# ANA_FE_1_2.net
KiCad netlist of a schematic drawn in Altium Designer
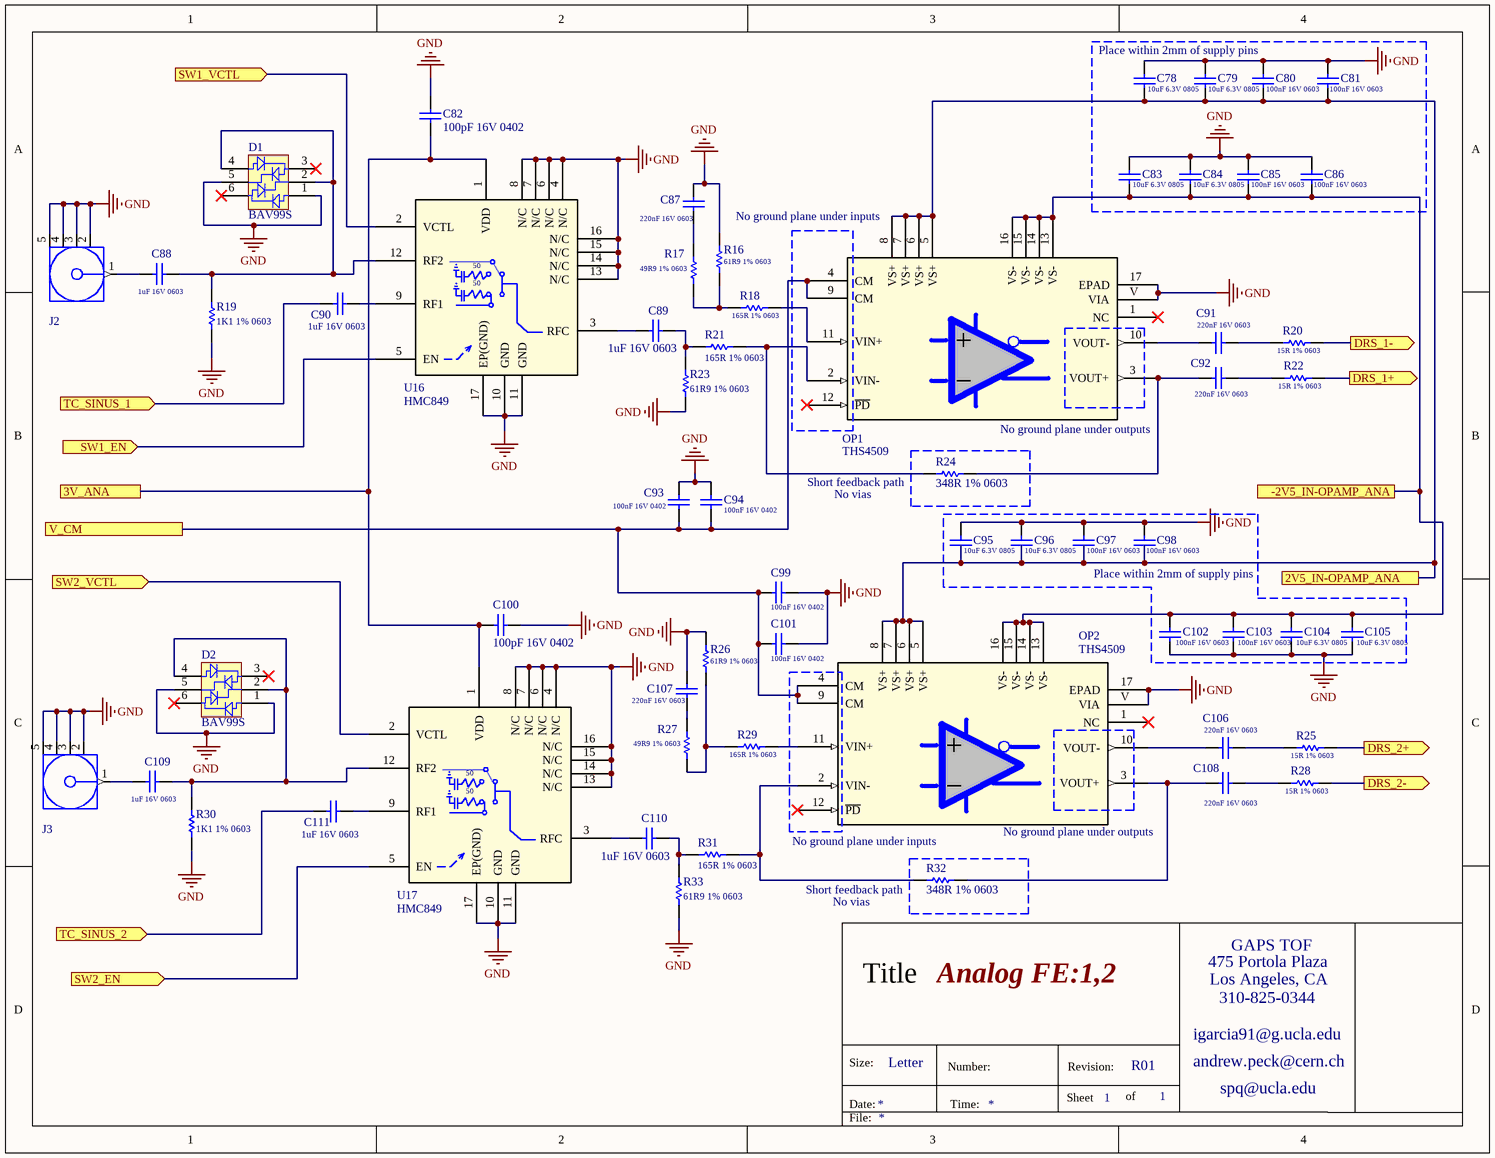
[diagram p0: ANA_FE_1_2.SchDoc]

(export (version "E")
  (design (tool "Eeschema 10.0.6"))
  (components
    (comp (ref "C78")
      (value "10uF 6.3V 0805")
      (footprint "CAPC0805(2012)145_L")
      (description "CAP 10uF 6.3V ±10% 0805 (2012 Metric) Thickness 1.45mm SMD")
      (fields (field (name "TOLERANCE") "Â±10%"))
      (libsource (lib "Altium Content Vault") (part "CAP"))
    )
    (comp (ref "C79")
      (value "10uF 6.3V 0805")
      (footprint "CAPC0805(2012)145_L")
      (description "CAP 10uF 6.3V ±10% 0805 (2012 Metric) Thickness 1.45mm SMD")
      (fields (field (name "TOLERANCE") "Â±10%"))
      (libsource (lib "Altium Content Vault") (part "CAP"))
    )
    (comp (ref "C80")
      (value "100nF 16V 0603")
      (footprint "CAPC0603(1608)100_N")
      (description "CAP 100nF 16V ±20% 0603 (1608 Metric) Thickness 1mm SMD")
      (fields (field (name "TOLERANCE") "Â±20%"))
      (libsource (lib "Altium Content Vault") (part "CAP"))
    )
    (comp (ref "C81")
      (value "100nF 16V 0603")
      (footprint "CAPC0603(1608)100_N")
      (description "CAP 100nF 16V ±20% 0603 (1608 Metric) Thickness 1mm SMD")
      (fields (field (name "TOLERANCE") "Â±20%"))
      (libsource (lib "Altium Content Vault") (part "CAP"))
    )
    (comp (ref "C82")
      (value "100pF 16V 0402")
      (footprint "CAPC0402(1005)60_M")
      (description "CAP 100pF 16V ±5% 0402 (1005 Metric) Thickness 0.6mm SMD")
      (fields (field (name "TOLERANCE") "Â±5%"))
      (libsource (lib "Altium Content Vault") (part "CAP"))
    )
    (comp (ref "C83")
      (value "10uF 6.3V 0805")
      (footprint "CAPC0805(2012)145_L")
      (description "CAP 10uF 6.3V ±10% 0805 (2012 Metric) Thickness 1.45mm SMD")
      (fields (field (name "TOLERANCE") "Â±10%"))
      (libsource (lib "Altium Content Vault") (part "CAP"))
    )
    (comp (ref "C84")
      (value "10uF 6.3V 0805")
      (footprint "CAPC0805(2012)145_L")
      (description "CAP 10uF 6.3V ±10% 0805 (2012 Metric) Thickness 1.45mm SMD")
      (fields (field (name "TOLERANCE") "Â±10%"))
      (libsource (lib "Altium Content Vault") (part "CAP"))
    )
    (comp (ref "C85")
      (value "100nF 16V 0603")
      (footprint "CAPC0603(1608)100_N")
      (description "CAP 100nF 16V ±20% 0603 (1608 Metric) Thickness 1mm SMD")
      (fields (field (name "TOLERANCE") "Â±20%"))
      (libsource (lib "Altium Content Vault") (part "CAP"))
    )
    (comp (ref "C86")
      (value "100nF 16V 0603")
      (footprint "CAPC0603(1608)100_N")
      (description "CAP 100nF 16V ±20% 0603 (1608 Metric) Thickness 1mm SMD")
      (fields (field (name "TOLERANCE") "Â±20%"))
      (libsource (lib "Altium Content Vault") (part "CAP"))
    )
    (comp (ref "C87")
      (value "220nF 16V 0603")
      (footprint "CAPC0603(1608)100_M")
      (description "CAP 220nF 16V ±10% 0603 (1608 Metric) Thickness 1mm SMD")
      (fields (field (name "TOLERANCE") "Â±10%"))
      (libsource (lib "Altium Content Vault") (part "CAP"))
    )
    (comp (ref "C88")
      (value "1uF 16V 0603")
      (footprint "CAPC0603(1608)100_N")
      (description "CAP 1uF 16V ±5% 0603 (1608 Metric) Thickness 1mm SMD")
      (fields (field (name "TOLERANCE") "Â±5%"))
      (libsource (lib "Altium Content Vault") (part "CAP"))
    )
    (comp (ref "C89")
      (value "1uF 16V 0603")
      (footprint "CAPC0603(1608)100_N")
      (description "CAP 1uF 16V ±5% 0603 (1608 Metric) Thickness 1mm SMD")
      (fields (field (name "TOLERANCE") "Â±5%"))
      (libsource (lib "Altium Content Vault") (part "CAP"))
    )
    (comp (ref "C90")
      (value "1uF 16V 0603")
      (footprint "CAPC0603(1608)100_N")
      (description "CAP 1uF 16V ±5% 0603 (1608 Metric) Thickness 1mm SMD")
      (fields (field (name "TOLERANCE") "Â±5%"))
      (libsource (lib "Altium Content Vault") (part "CAP"))
    )
    (comp (ref "C91")
      (value "220nF 16V 0603")
      (footprint "CAPC0603(1608)100_M")
      (description "CAP 220nF 16V ±10% 0603 (1608 Metric) Thickness 1mm SMD")
      (fields (field (name "TOLERANCE") "Â±10%"))
      (libsource (lib "Altium Content Vault") (part "CAP"))
    )
    (comp (ref "C92")
      (value "220nF 16V 0603")
      (footprint "CAPC0603(1608)100_M")
      (description "CAP 220nF 16V ±10% 0603 (1608 Metric) Thickness 1mm SMD")
      (fields (field (name "TOLERANCE") "Â±10%"))
      (libsource (lib "Altium Content Vault") (part "CAP"))
    )
    (comp (ref "C93")
      (value "100nF 16V 0402")
      (footprint "CAPC0402(1005)60_M")
      (description "CAP 100nF 16V ±20% 0402 (1005 Metric) Thickness 0.6mm SMD")
      (fields (field (name "TOLERANCE") "Â±20%"))
      (libsource (lib "Altium Content Vault") (part "CAP"))
    )
    (comp (ref "C94")
      (value "100nF 16V 0402")
      (footprint "CAPC0402(1005)60_M")
      (description "CAP 100nF 16V ±20% 0402 (1005 Metric) Thickness 0.6mm SMD")
      (fields (field (name "TOLERANCE") "Â±20%"))
      (libsource (lib "Altium Content Vault") (part "CAP"))
    )
    (comp (ref "C95")
      (value "10uF 6.3V 0805")
      (footprint "CAPC0805(2012)145_L")
      (description "CAP 10uF 6.3V ±10% 0805 (2012 Metric) Thickness 1.45mm SMD")
      (fields (field (name "TOLERANCE") "Â±10%"))
      (libsource (lib "Altium Content Vault") (part "CAP"))
    )
    (comp (ref "C96")
      (value "10uF 6.3V 0805")
      (footprint "CAPC0805(2012)145_L")
      (description "CAP 10uF 6.3V ±10% 0805 (2012 Metric) Thickness 1.45mm SMD")
      (fields (field (name "TOLERANCE") "Â±10%"))
      (libsource (lib "Altium Content Vault") (part "CAP"))
    )
    (comp (ref "C97")
      (value "100nF 16V 0603")
      (footprint "CAPC0603(1608)100_N")
      (description "CAP 100nF 16V ±20% 0603 (1608 Metric) Thickness 1mm SMD")
      (fields (field (name "TOLERANCE") "Â±20%"))
      (libsource (lib "Altium Content Vault") (part "CAP"))
    )
    (comp (ref "C98")
      (value "100nF 16V 0603")
      (footprint "CAPC0603(1608)100_N")
      (description "CAP 100nF 16V ±20% 0603 (1608 Metric) Thickness 1mm SMD")
      (fields (field (name "TOLERANCE") "Â±20%"))
      (libsource (lib "Altium Content Vault") (part "CAP"))
    )
    (comp (ref "C99")
      (value "100nF 16V 0402")
      (footprint "CAPC0402(1005)60_M")
      (description "CAP 100nF 16V ±20% 0402 (1005 Metric) Thickness 0.6mm SMD")
      (fields (field (name "TOLERANCE") "Â±20%"))
      (libsource (lib "Altium Content Vault") (part "CAP"))
    )
    (comp (ref "C100")
      (value "100pF 16V 0402")
      (footprint "CAPC0402(1005)60_M")
      (description "CAP 100pF 16V ±5% 0402 (1005 Metric) Thickness 0.6mm SMD")
      (fields (field (name "TOLERANCE") "Â±5%"))
      (libsource (lib "Altium Content Vault") (part "CAP"))
    )
    (comp (ref "C101")
      (value "100nF 16V 0402")
      (footprint "CAPC0402(1005)60_M")
      (description "CAP 100nF 16V ±20% 0402 (1005 Metric) Thickness 0.6mm SMD")
      (fields (field (name "TOLERANCE") "Â±20%"))
      (libsource (lib "Altium Content Vault") (part "CAP"))
    )
    (comp (ref "C102")
      (value "100nF 16V 0603")
      (footprint "CAPC0603(1608)100_N")
      (description "CAP 100nF 16V ±20% 0603 (1608 Metric) Thickness 1mm SMD")
      (fields (field (name "TOLERANCE") "Â±20%"))
      (libsource (lib "Altium Content Vault") (part "CAP"))
    )
    (comp (ref "C103")
      (value "100nF 16V 0603")
      (footprint "CAPC0603(1608)100_N")
      (description "CAP 100nF 16V ±20% 0603 (1608 Metric) Thickness 1mm SMD")
      (fields (field (name "TOLERANCE") "Â±20%"))
      (libsource (lib "Altium Content Vault") (part "CAP"))
    )
    (comp (ref "C104")
      (value "10uF 6.3V 0805")
      (footprint "CAPC0805(2012)145_L")
      (description "CAP 10uF 6.3V ±10% 0805 (2012 Metric) Thickness 1.45mm SMD")
      (fields (field (name "TOLERANCE") "Â±10%"))
      (libsource (lib "Altium Content Vault") (part "CAP"))
    )
    (comp (ref "C105")
      (value "10uF 6.3V 0805")
      (footprint "CAPC0805(2012)145_L")
      (description "CAP 10uF 6.3V ±10% 0805 (2012 Metric) Thickness 1.45mm SMD")
      (fields (field (name "TOLERANCE") "Â±10%"))
      (libsource (lib "Altium Content Vault") (part "CAP"))
    )
    (comp (ref "C106")
      (value "220nF 16V 0603")
      (footprint "CAPC0603(1608)100_M")
      (description "CAP 220nF 16V ±10% 0603 (1608 Metric) Thickness 1mm SMD")
      (fields (field (name "TOLERANCE") "Â±10%"))
      (libsource (lib "Altium Content Vault") (part "CAP"))
    )
    (comp (ref "C107")
      (value "220nF 16V 0603")
      (footprint "CAPC0603(1608)100_M")
      (description "CAP 220nF 16V ±10% 0603 (1608 Metric) Thickness 1mm SMD")
      (fields (field (name "TOLERANCE") "Â±10%"))
      (libsource (lib "Altium Content Vault") (part "CAP"))
    )
    (comp (ref "C108")
      (value "220nF 16V 0603")
      (footprint "CAPC0603(1608)100_M")
      (description "CAP 220nF 16V ±10% 0603 (1608 Metric) Thickness 1mm SMD")
      (fields (field (name "TOLERANCE") "Â±10%"))
      (libsource (lib "Altium Content Vault") (part "CAP"))
    )
    (comp (ref "C109")
      (value "1uF 16V 0603")
      (footprint "CAPC0603(1608)100_N")
      (description "CAP 1uF 16V ±5% 0603 (1608 Metric) Thickness 1mm SMD")
      (fields (field (name "TOLERANCE") "Â±5%"))
      (libsource (lib "Altium Content Vault") (part "CAP"))
    )
    (comp (ref "C110")
      (value "1uF 16V 0603")
      (footprint "CAPC0603(1608)100_N")
      (description "CAP 1uF 16V ±5% 0603 (1608 Metric) Thickness 1mm SMD")
      (fields (field (name "TOLERANCE") "Â±5%"))
      (libsource (lib "Altium Content Vault") (part "CAP"))
    )
    (comp (ref "C111")
      (value "1uF 16V 0603")
      (footprint "CAPC0603(1608)100_N")
      (description "CAP 1uF 16V ±5% 0603 (1608 Metric) Thickness 1mm SMD")
      (fields (field (name "TOLERANCE") "Â±5%"))
      (libsource (lib "Altium Content Vault") (part "CAP"))
    )
    (comp (ref "D1")
      (value "BAV99S")
      (footprint "INF-SOT363_V")
      (description "Silicon Switching Diode, SOT363, Reel, Green")
      (fields (field (name "MANUFACTURER") "Infineon"))
      (libsource (lib "Altium Content Vault") (part "INF-D_A1K2C3A4K5C6-6"))
    )
    (comp (ref "D2")
      (value "BAV99S")
      (footprint "INF-SOT363_V")
      (description "Silicon Switching Diode, SOT363, Reel, Green")
      (fields (field (name "MANUFACTURER") "Infineon"))
      (libsource (lib "Altium Content Vault") (part "INF-D_A1K2C3A4K5C6-6"))
    )
    (comp (ref "J2")
      (value "CONREVSMA003.062")
      (footprint "CON-SMA-EDGE062")
      (libsource (lib "Altium Content Vault") (part "CN-1P-F-RF5"))
    )
    (comp (ref "J3")
      (value "CONREVSMA003.062")
      (footprint "CON-SMA-EDGE062")
      (libsource (lib "Altium Content Vault") (part "CN-1P-F-RF5"))
    )
    (comp (ref "OP1")
      (value "THS4509")
      (footprint "RGT16")
      (description "Imported")
      (fields (field (name "MANUFACTURER_PART_NUMBER") "THS4509RGTT"))
      (libsource (lib "THS4509RGTT") (part "THS4509RGTT"))
    )
    (comp (ref "OP2")
      (value "THS4509")
      (footprint "RGT16")
      (description "Imported")
      (fields (field (name "MANUFACTURER_PART_NUMBER") "THS4509RGTT"))
      (libsource (lib "THS4509RGTT") (part "THS4509RGTT"))
    )
    (comp (ref "R16")
      (value "61R9 1% 0603")
      (footprint "RESC0603(1608)_M")
      (description "61R9 0.1W 1% 0603 (1608 Metric)  SMD")
      (fields (field (name "TOLERANCE") "1 %") (field (name "POWER") "0.1 W"))
      (libsource (lib "Altium Content Vault") (part "RES"))
    )
    (comp (ref "R17")
      (value "49R9 1% 0603")
      (footprint "RESC0603(1608)_N")
      (description "49R9 0.1W 1% 0603 (1608 Metric)  SMD")
      (fields (field (name "POWER") "0.1 W") (field (name "TOLERANCE") "1 %"))
      (libsource (lib "Altium Content Vault") (part "RES"))
    )
    (comp (ref "R18")
      (value "165R 1% 0603")
      (footprint "RESC0603(1608)_M")
      (description "165R 0.1W 1% 0603 (1608 Metric)  SMD")
      (fields (field (name "TOLERANCE") "1 %") (field (name "POWER") "0.1 W"))
      (libsource (lib "Altium Content Vault") (part "RES"))
    )
    (comp (ref "R19")
      (value "1K1 1% 0603")
      (footprint "RESC0603(1608)_N")
      (description "1K1 0.1W 1% 0603 (1608 Metric)  SMD")
      (fields (field (name "TOLERANCE") "1 %") (field (name "POWER") "0.1 W"))
      (libsource (lib "Altium Content Vault") (part "RES"))
    )
    (comp (ref "R20")
      (value "15R 1% 0603")
      (footprint "RESC0603(1608)_M")
      (description "15R 0.1W 1% 0603 (1608 Metric)  SMD")
      (fields (field (name "TOLERANCE") "1 %") (field (name "POWER") "0.1 W"))
      (libsource (lib "Altium Content Vault") (part "RES"))
    )
    (comp (ref "R21")
      (value "165R 1% 0603")
      (footprint "RESC0603(1608)_M")
      (description "165R 0.1W 1% 0603 (1608 Metric)  SMD")
      (fields (field (name "TOLERANCE") "1 %") (field (name "POWER") "0.1 W"))
      (libsource (lib "Altium Content Vault") (part "RES"))
    )
    (comp (ref "R22")
      (value "15R 1% 0603")
      (footprint "RESC0603(1608)_M")
      (description "15R 0.1W 1% 0603 (1608 Metric)  SMD")
      (fields (field (name "TOLERANCE") "1 %") (field (name "POWER") "0.1 W"))
      (libsource (lib "Altium Content Vault") (part "RES"))
    )
    (comp (ref "R23")
      (value "61R9 1% 0603")
      (footprint "RESC0603(1608)_M")
      (description "61R9 0.1W 1% 0603 (1608 Metric)  SMD")
      (fields (field (name "TOLERANCE") "1 %") (field (name "POWER") "0.1 W"))
      (libsource (lib "Altium Content Vault") (part "RES"))
    )
    (comp (ref "R24")
      (value "348R 1% 0603")
      (footprint "RESC0603(1608)_N")
      (description "348R 0.1W 1% 0603 (1608 Metric)  SMD")
      (fields (field (name "POWER") "0.1 W") (field (name "TOLERANCE") "1 %"))
      (libsource (lib "Altium Content Vault") (part "RES"))
    )
    (comp (ref "R25")
      (value "15R 1% 0603")
      (footprint "RESC0603(1608)_M")
      (description "15R 0.1W 1% 0603 (1608 Metric)  SMD")
      (fields (field (name "TOLERANCE") "1 %") (field (name "POWER") "0.1 W"))
      (libsource (lib "Altium Content Vault") (part "RES"))
    )
    (comp (ref "R26")
      (value "61R9 1% 0603")
      (footprint "RESC0603(1608)_M")
      (description "61R9 0.1W 1% 0603 (1608 Metric)  SMD")
      (fields (field (name "TOLERANCE") "1 %") (field (name "POWER") "0.1 W"))
      (libsource (lib "Altium Content Vault") (part "RES"))
    )
    (comp (ref "R27")
      (value "49R9 1% 0603")
      (footprint "RESC0603(1608)_N")
      (description "49R9 0.1W 1% 0603 (1608 Metric)  SMD")
      (fields (field (name "POWER") "0.1 W") (field (name "TOLERANCE") "1 %"))
      (libsource (lib "Altium Content Vault") (part "RES"))
    )
    (comp (ref "R28")
      (value "15R 1% 0603")
      (footprint "RESC0603(1608)_M")
      (description "15R 0.1W 1% 0603 (1608 Metric)  SMD")
      (fields (field (name "TOLERANCE") "1 %") (field (name "POWER") "0.1 W"))
      (libsource (lib "Altium Content Vault") (part "RES"))
    )
    (comp (ref "R29")
      (value "165R 1% 0603")
      (footprint "RESC0603(1608)_M")
      (description "165R 0.1W 1% 0603 (1608 Metric)  SMD")
      (fields (field (name "TOLERANCE") "1 %") (field (name "POWER") "0.1 W"))
      (libsource (lib "Altium Content Vault") (part "RES"))
    )
    (comp (ref "R30")
      (value "1K1 1% 0603")
      (footprint "RESC0603(1608)_N")
      (description "1K1 0.1W 1% 0603 (1608 Metric)  SMD")
      (fields (field (name "TOLERANCE") "1 %") (field (name "POWER") "0.1 W"))
      (libsource (lib "Altium Content Vault") (part "RES"))
    )
    (comp (ref "R31")
      (value "165R 1% 0603")
      (footprint "RESC0603(1608)_M")
      (description "165R 0.1W 1% 0603 (1608 Metric)  SMD")
      (fields (field (name "TOLERANCE") "1 %") (field (name "POWER") "0.1 W"))
      (libsource (lib "Altium Content Vault") (part "RES"))
    )
    (comp (ref "R32")
      (value "348R 1% 0603")
      (footprint "RESC0603(1608)_N")
      (description "348R 0.1W 1% 0603 (1608 Metric)  SMD")
      (fields (field (name "POWER") "0.1 W") (field (name "TOLERANCE") "1 %"))
      (libsource (lib "Altium Content Vault") (part "RES"))
    )
    (comp (ref "R33")
      (value "61R9 1% 0603")
      (footprint "RESC0603(1608)_M")
      (description "61R9 0.1W 1% 0603 (1608 Metric)  SMD")
      (fields (field (name "TOLERANCE") "1 %") (field (name "POWER") "0.1 W"))
      (libsource (lib "Altium Content Vault") (part "RES"))
    )
    (comp (ref "U16")
      (value "HMC849")
      (footprint "CP_16_40")
      (description "Imported")
      (fields (field (name "MANUFACTURER_PART_NUMBER") "HMC849ALP4CE"))
      (libsource (lib "HMC849ALP4CE") (part "HMC849ALP4CE"))
    )
    (comp (ref "U17")
      (value "HMC849")
      (footprint "CP_16_40")
      (description "Imported")
      (fields (field (name "MANUFACTURER_PART_NUMBER") "HMC849ALP4CE"))
      (libsource (lib "HMC849ALP4CE") (part "HMC849ALP4CE"))
    )
  )
  (nets
    (net (code "1") (name "/-2V5_IN-OPAMP_ANA") (class "Default")
      (node (ref "C102") (pin "1") (pinfunction "1_1") (pintype "passive"))
      (node (ref "C103") (pin "1") (pinfunction "1_1") (pintype "passive"))
      (node (ref "C104") (pin "1") (pinfunction "1_1") (pintype "passive"))
      (node (ref "C105") (pin "1") (pinfunction "1_1") (pintype "passive"))
      (node (ref "C83") (pin "1") (pinfunction "1_1") (pintype "passive"))
      (node (ref "C84") (pin "1") (pinfunction "1_1") (pintype "passive"))
      (node (ref "C85") (pin "1") (pinfunction "1_1") (pintype "passive"))
      (node (ref "C86") (pin "1") (pinfunction "1_1") (pintype "passive"))
      (node (ref "OP1") (pin "13") (pinfunction "VS-_13") (pintype "power_in"))
      (node (ref "OP1") (pin "14") (pinfunction "VS-_14") (pintype "power_in"))
      (node (ref "OP1") (pin "15") (pinfunction "VS-_15") (pintype "power_in"))
      (node (ref "OP1") (pin "16") (pinfunction "VS-_16") (pintype "power_in"))
      (node (ref "OP2") (pin "13") (pinfunction "VS-_13") (pintype "power_in"))
      (node (ref "OP2") (pin "14") (pinfunction "VS-_14") (pintype "power_in"))
      (node (ref "OP2") (pin "15") (pinfunction "VS-_15") (pintype "power_in"))
      (node (ref "OP2") (pin "16") (pinfunction "VS-_16") (pintype "power_in"))
    )
    (net (code "2") (name "/2V5_IN-OPAMP_ANA") (class "Default")
      (node (ref "C78") (pin "1") (pinfunction "1_1") (pintype "passive"))
      (node (ref "C79") (pin "1") (pinfunction "1_1") (pintype "passive"))
      (node (ref "C80") (pin "1") (pinfunction "1_1") (pintype "passive"))
      (node (ref "C81") (pin "1") (pinfunction "1_1") (pintype "passive"))
      (node (ref "C95") (pin "1") (pinfunction "1_1") (pintype "passive"))
      (node (ref "C96") (pin "1") (pinfunction "1_1") (pintype "passive"))
      (node (ref "C97") (pin "1") (pinfunction "1_1") (pintype "passive"))
      (node (ref "C98") (pin "1") (pinfunction "1_1") (pintype "passive"))
      (node (ref "OP1") (pin "5") (pinfunction "VS+_5") (pintype "power_in"))
      (node (ref "OP1") (pin "6") (pinfunction "VS+_6") (pintype "power_in"))
      (node (ref "OP1") (pin "7") (pinfunction "VS+_7") (pintype "power_in"))
      (node (ref "OP1") (pin "8") (pinfunction "VS+_8") (pintype "power_in"))
      (node (ref "OP2") (pin "5") (pinfunction "VS+_5") (pintype "power_in"))
      (node (ref "OP2") (pin "6") (pinfunction "VS+_6") (pintype "power_in"))
      (node (ref "OP2") (pin "7") (pinfunction "VS+_7") (pintype "power_in"))
      (node (ref "OP2") (pin "8") (pinfunction "VS+_8") (pintype "power_in"))
    )
    (net (code "3") (name "/3V_ANA") (class "Default")
      (node (ref "C100") (pin "2") (pinfunction "2_2") (pintype "passive"))
      (node (ref "C82") (pin "1") (pinfunction "1_1") (pintype "passive"))
      (node (ref "U16") (pin "1") (pinfunction "VDD_1") (pintype "passive"))
      (node (ref "U17") (pin "1") (pinfunction "VDD_1") (pintype "passive"))
    )
    (net (code "4") (name "/DRS_1+") (class "Default")
      (node (ref "R22") (pin "2") (pinfunction "2_2") (pintype "passive"))
    )
    (net (code "5") (name "/DRS_1-") (class "Default")
      (node (ref "R20") (pin "2") (pinfunction "2_2") (pintype "passive"))
    )
    (net (code "6") (name "/DRS_2+") (class "Default")
      (node (ref "R25") (pin "2") (pinfunction "2_2") (pintype "passive"))
    )
    (net (code "7") (name "/DRS_2-") (class "Default")
      (node (ref "R28") (pin "2") (pinfunction "2_2") (pintype "passive"))
    )
    (net (code "8") (name "/SW1_EN") (class "Default")
      (node (ref "U16") (pin "5") (pinfunction "EN_5") (pintype "passive"))
    )
    (net (code "9") (name "/SW1_VCTL") (class "Default")
      (node (ref "U16") (pin "2") (pinfunction "VCTL_2") (pintype "passive"))
    )
    (net (code "10") (name "/SW2_EN") (class "Default")
      (node (ref "U17") (pin "5") (pinfunction "EN_5") (pintype "passive"))
    )
    (net (code "11") (name "/SW2_VCTL") (class "Default")
      (node (ref "U17") (pin "2") (pinfunction "VCTL_2") (pintype "passive"))
    )
    (net (code "12") (name "/TC_SINUS_1") (class "Default")
      (node (ref "C90") (pin "1") (pinfunction "1_1") (pintype "passive"))
    )
    (net (code "13") (name "/TC_SINUS_2") (class "Default")
      (node (ref "C111") (pin "1") (pinfunction "1_1") (pintype "passive"))
    )
    (net (code "14") (name "/V_CM") (class "Default")
      (node (ref "C101") (pin "2") (pinfunction "2_2") (pintype "passive"))
      (node (ref "C93") (pin "2") (pinfunction "2_2") (pintype "passive"))
      (node (ref "C94") (pin "2") (pinfunction "2_2") (pintype "passive"))
      (node (ref "C99") (pin "2") (pinfunction "2_2") (pintype "passive"))
      (node (ref "OP1") (pin "4") (pinfunction "CM_4") (pintype "passive"))
      (node (ref "OP1") (pin "9") (pinfunction "CM_9") (pintype "passive"))
      (node (ref "OP2") (pin "4") (pinfunction "CM_4") (pintype "passive"))
      (node (ref "OP2") (pin "9") (pinfunction "CM_9") (pintype "passive"))
    )
    (net (code "15") (name "GND") (class "Default")
      (node (ref "C100") (pin "1") (pinfunction "1_1") (pintype "passive"))
      (node (ref "C101") (pin "1") (pinfunction "1_1") (pintype "passive"))
      (node (ref "C102") (pin "2") (pinfunction "2_2") (pintype "passive"))
      (node (ref "C103") (pin "2") (pinfunction "2_2") (pintype "passive"))
      (node (ref "C104") (pin "2") (pinfunction "2_2") (pintype "passive"))
      (node (ref "C105") (pin "2") (pinfunction "2_2") (pintype "passive"))
      (node (ref "C107") (pin "2") (pinfunction "2_2") (pintype "passive"))
      (node (ref "C78") (pin "2") (pinfunction "2_2") (pintype "passive"))
      (node (ref "C79") (pin "2") (pinfunction "2_2") (pintype "passive"))
      (node (ref "C80") (pin "2") (pinfunction "2_2") (pintype "passive"))
      (node (ref "C81") (pin "2") (pinfunction "2_2") (pintype "passive"))
      (node (ref "C82") (pin "2") (pinfunction "2_2") (pintype "passive"))
      (node (ref "C83") (pin "2") (pinfunction "2_2") (pintype "passive"))
      (node (ref "C84") (pin "2") (pinfunction "2_2") (pintype "passive"))
      (node (ref "C85") (pin "2") (pinfunction "2_2") (pintype "passive"))
      (node (ref "C86") (pin "2") (pinfunction "2_2") (pintype "passive"))
      (node (ref "C87") (pin "2") (pinfunction "2_2") (pintype "passive"))
      (node (ref "C93") (pin "1") (pinfunction "1_1") (pintype "passive"))
      (node (ref "C94") (pin "1") (pinfunction "1_1") (pintype "passive"))
      (node (ref "C95") (pin "2") (pinfunction "2_2") (pintype "passive"))
      (node (ref "C96") (pin "2") (pinfunction "2_2") (pintype "passive"))
      (node (ref "C97") (pin "2") (pinfunction "2_2") (pintype "passive"))
      (node (ref "C98") (pin "2") (pinfunction "2_2") (pintype "passive"))
      (node (ref "C99") (pin "1") (pinfunction "1_1") (pintype "passive"))
      (node (ref "D1") (pin "1") (pinfunction "A1_1") (pintype "passive"))
      (node (ref "D1") (pin "5") (pinfunction "K5_5") (pintype "passive"))
      (node (ref "D2") (pin "1") (pinfunction "A1_1") (pintype "passive"))
      (node (ref "D2") (pin "5") (pinfunction "K5_5") (pintype "passive"))
      (node (ref "J2") (pin "2") (pinfunction "GND_2") (pintype "power_in"))
      (node (ref "J2") (pin "3") (pinfunction "GND_3") (pintype "power_in"))
      (node (ref "J2") (pin "4") (pinfunction "GND_4") (pintype "power_in"))
      (node (ref "J2") (pin "5") (pinfunction "GND_5") (pintype "power_in"))
      (node (ref "J3") (pin "2") (pinfunction "GND_2") (pintype "power_in"))
      (node (ref "J3") (pin "3") (pinfunction "GND_3") (pintype "power_in"))
      (node (ref "J3") (pin "4") (pinfunction "GND_4") (pintype "power_in"))
      (node (ref "J3") (pin "5") (pinfunction "GND_5") (pintype "power_in"))
      (node (ref "OP1") (pin "17") (pinfunction "EPAD_17") (pintype "passive"))
      (node (ref "OP1") (pin "V") (pinfunction "VIA_V") (pintype "passive"))
      (node (ref "OP2") (pin "17") (pinfunction "EPAD_17") (pintype "passive"))
      (node (ref "OP2") (pin "V") (pinfunction "VIA_V") (pintype "passive"))
      (node (ref "R16") (pin "2") (pinfunction "2_2") (pintype "passive"))
      (node (ref "R19") (pin "1") (pinfunction "1_1") (pintype "passive"))
      (node (ref "R23") (pin "1") (pinfunction "1_1") (pintype "passive"))
      (node (ref "R26") (pin "2") (pinfunction "2_2") (pintype "passive"))
      (node (ref "R30") (pin "1") (pinfunction "1_1") (pintype "passive"))
      (node (ref "R33") (pin "1") (pinfunction "1_1") (pintype "passive"))
      (node (ref "U16") (pin "10") (pinfunction "GND_10") (pintype "passive"))
      (node (ref "U16") (pin "11") (pinfunction "GND_11") (pintype "passive"))
      (node (ref "U16") (pin "13") (pinfunction "N/C_13") (pintype "passive"))
      (node (ref "U16") (pin "14") (pinfunction "N/C_14") (pintype "passive"))
      (node (ref "U16") (pin "15") (pinfunction "N/C_15") (pintype "passive"))
      (node (ref "U16") (pin "16") (pinfunction "N/C_16") (pintype "passive"))
      (node (ref "U16") (pin "17") (pinfunction "EP(GND)_17") (pintype "passive"))
      (node (ref "U16") (pin "4") (pinfunction "N/C_4") (pintype "passive"))
      (node (ref "U16") (pin "6") (pinfunction "N/C_6") (pintype "passive"))
      (node (ref "U16") (pin "7") (pinfunction "N/C_7") (pintype "passive"))
      (node (ref "U16") (pin "8") (pinfunction "N/C_8") (pintype "passive"))
      (node (ref "U17") (pin "10") (pinfunction "GND_10") (pintype "passive"))
      (node (ref "U17") (pin "11") (pinfunction "GND_11") (pintype "passive"))
      (node (ref "U17") (pin "13") (pinfunction "N/C_13") (pintype "passive"))
      (node (ref "U17") (pin "14") (pinfunction "N/C_14") (pintype "passive"))
      (node (ref "U17") (pin "15") (pinfunction "N/C_15") (pintype "passive"))
      (node (ref "U17") (pin "16") (pinfunction "N/C_16") (pintype "passive"))
      (node (ref "U17") (pin "17") (pinfunction "EP(GND)_17") (pintype "passive"))
      (node (ref "U17") (pin "4") (pinfunction "N/C_4") (pintype "passive"))
      (node (ref "U17") (pin "6") (pinfunction "N/C_6") (pintype "passive"))
      (node (ref "U17") (pin "7") (pinfunction "N/C_7") (pintype "passive"))
      (node (ref "U17") (pin "8") (pinfunction "N/C_8") (pintype "passive"))
    )
    (net (code "16") (name "Net-(C87-Pad1)") (class "Default")
      (node (ref "C87") (pin "1") (pinfunction "1_1") (pintype "passive"))
      (node (ref "R17") (pin "2") (pinfunction "2_2") (pintype "passive"))
    )
    (net (code "17") (name "Net-(C89-Pad2)") (class "Default")
      (node (ref "C89") (pin "2") (pinfunction "2_2") (pintype "passive"))
      (node (ref "R21") (pin "1") (pinfunction "1_1") (pintype "passive"))
      (node (ref "R23") (pin "2") (pinfunction "2_2") (pintype "passive"))
    )
    (net (code "18") (name "Net-(C91-Pad1)") (class "Default")
      (node (ref "C91") (pin "1") (pinfunction "1_1") (pintype "passive"))
      (node (ref "R20") (pin "1") (pinfunction "1_1") (pintype "passive"))
    )
    (net (code "19") (name "Net-(C92-Pad1)") (class "Default")
      (node (ref "C92") (pin "1") (pinfunction "1_1") (pintype "passive"))
      (node (ref "R22") (pin "1") (pinfunction "1_1") (pintype "passive"))
    )
    (net (code "20") (name "Net-(C106-Pad1)") (class "Default")
      (node (ref "C106") (pin "1") (pinfunction "1_1") (pintype "passive"))
      (node (ref "R25") (pin "1") (pinfunction "1_1") (pintype "passive"))
    )
    (net (code "21") (name "Net-(C107-Pad1)") (class "Default")
      (node (ref "C107") (pin "1") (pinfunction "1_1") (pintype "passive"))
      (node (ref "R27") (pin "2") (pinfunction "2_2") (pintype "passive"))
    )
    (net (code "22") (name "Net-(C108-Pad1)") (class "Default")
      (node (ref "C108") (pin "1") (pinfunction "1_1") (pintype "passive"))
      (node (ref "R28") (pin "1") (pinfunction "1_1") (pintype "passive"))
    )
    (net (code "23") (name "Net-(C110-Pad2)") (class "Default")
      (node (ref "C110") (pin "2") (pinfunction "2_2") (pintype "passive"))
      (node (ref "R31") (pin "1") (pinfunction "1_1") (pintype "passive"))
      (node (ref "R33") (pin "2") (pinfunction "2_2") (pintype "passive"))
    )
    (net (code "24") (name "Net-(D1-A4)") (class "Default")
      (node (ref "C88") (pin "2") (pinfunction "2_2") (pintype "passive"))
      (node (ref "D1") (pin "2") (pinfunction "K2_2") (pintype "passive"))
      (node (ref "D1") (pin "4") (pinfunction "A4_4") (pintype "passive"))
      (node (ref "R19") (pin "2") (pinfunction "2_2") (pintype "passive"))
      (node (ref "U16") (pin "12") (pinfunction "RF2_12") (pintype "passive"))
    )
    (net (code "25") (name "Net-(D2-A4)") (class "Default")
      (node (ref "C109") (pin "2") (pinfunction "2_2") (pintype "passive"))
      (node (ref "D2") (pin "2") (pinfunction "K2_2") (pintype "passive"))
      (node (ref "D2") (pin "4") (pinfunction "A4_4") (pintype "passive"))
      (node (ref "R30") (pin "2") (pinfunction "2_2") (pintype "passive"))
      (node (ref "U17") (pin "12") (pinfunction "RF2_12") (pintype "passive"))
    )
    (net (code "26") (name "Net-(J2-Signal)") (class "Default")
      (node (ref "C88") (pin "1") (pinfunction "1_1") (pintype "passive"))
      (node (ref "J2") (pin "1") (pinfunction "Signal_1") (pintype "output"))
    )
    (net (code "27") (name "Net-(J3-Signal)") (class "Default")
      (node (ref "C109") (pin "1") (pinfunction "1_1") (pintype "passive"))
      (node (ref "J3") (pin "1") (pinfunction "Signal_1") (pintype "output"))
    )
    (net (code "28") (name "Net-(OP1-VIN+)") (class "Default")
      (node (ref "OP1") (pin "11") (pinfunction "VIN+_11") (pintype "input"))
      (node (ref "R18") (pin "2") (pinfunction "2_2") (pintype "passive"))
    )
    (net (code "29") (name "Net-(OP1-VIN-)") (class "Default")
      (node (ref "OP1") (pin "2") (pinfunction "VIN-_2") (pintype "input"))
      (node (ref "R21") (pin "2") (pinfunction "2_2") (pintype "passive"))
      (node (ref "R24") (pin "1") (pinfunction "1_1") (pintype "passive"))
    )
    (net (code "30") (name "Net-(OP1-VOUT+)") (class "Default")
      (node (ref "C92") (pin "2") (pinfunction "2_2") (pintype "passive"))
      (node (ref "OP1") (pin "3") (pinfunction "VOUT+_3") (pintype "output"))
      (node (ref "R24") (pin "2") (pinfunction "2_2") (pintype "passive"))
    )
    (net (code "31") (name "Net-(OP1-VOUT-)") (class "Default")
      (node (ref "C91") (pin "2") (pinfunction "2_2") (pintype "passive"))
      (node (ref "OP1") (pin "10") (pinfunction "VOUT-_10") (pintype "output"))
    )
    (net (code "32") (name "Net-(OP2-VIN+)") (class "Default")
      (node (ref "OP2") (pin "11") (pinfunction "VIN+_11") (pintype "input"))
      (node (ref "R29") (pin "2") (pinfunction "2_2") (pintype "passive"))
    )
    (net (code "33") (name "Net-(OP2-VIN-)") (class "Default")
      (node (ref "OP2") (pin "2") (pinfunction "VIN-_2") (pintype "input"))
      (node (ref "R31") (pin "2") (pinfunction "2_2") (pintype "passive"))
      (node (ref "R32") (pin "1") (pinfunction "1_1") (pintype "passive"))
    )
    (net (code "34") (name "Net-(OP2-VOUT+)") (class "Default")
      (node (ref "C108") (pin "2") (pinfunction "2_2") (pintype "passive"))
      (node (ref "OP2") (pin "3") (pinfunction "VOUT+_3") (pintype "output"))
      (node (ref "R32") (pin "2") (pinfunction "2_2") (pintype "passive"))
    )
    (net (code "35") (name "Net-(OP2-VOUT-)") (class "Default")
      (node (ref "C106") (pin "2") (pinfunction "2_2") (pintype "passive"))
      (node (ref "OP2") (pin "10") (pinfunction "VOUT-_10") (pintype "output"))
    )
    (net (code "36") (name "Net-(R16-Pad1)") (class "Default")
      (node (ref "R16") (pin "1") (pinfunction "1_1") (pintype "passive"))
      (node (ref "R17") (pin "1") (pinfunction "1_1") (pintype "passive"))
      (node (ref "R18") (pin "1") (pinfunction "1_1") (pintype "passive"))
    )
    (net (code "37") (name "Net-(R26-Pad1)") (class "Default")
      (node (ref "R26") (pin "1") (pinfunction "1_1") (pintype "passive"))
      (node (ref "R27") (pin "1") (pinfunction "1_1") (pintype "passive"))
      (node (ref "R29") (pin "1") (pinfunction "1_1") (pintype "passive"))
    )
    (net (code "38") (name "Net-(U16-RF1)") (class "Default")
      (node (ref "C90") (pin "2") (pinfunction "2_2") (pintype "passive"))
      (node (ref "U16") (pin "9") (pinfunction "RF1_9") (pintype "passive"))
    )
    (net (code "39") (name "Net-(U16-RFC)") (class "Default")
      (node (ref "C89") (pin "1") (pinfunction "1_1") (pintype "passive"))
      (node (ref "U16") (pin "3") (pinfunction "RFC_3") (pintype "passive"))
    )
    (net (code "40") (name "Net-(U17-RF1)") (class "Default")
      (node (ref "C111") (pin "2") (pinfunction "2_2") (pintype "passive"))
      (node (ref "U17") (pin "9") (pinfunction "RF1_9") (pintype "passive"))
    )
    (net (code "41") (name "Net-(U17-RFC)") (class "Default")
      (node (ref "C110") (pin "1") (pinfunction "1_1") (pintype "passive"))
      (node (ref "U17") (pin "3") (pinfunction "RFC_3") (pintype "passive"))
    )
    (net (code "42") (name "unconnected-(D1-C3-Pad3)") (class "Default")
      (node (ref "D1") (pin "3") (pinfunction "C3_3") (pintype "passive+no_connect"))
    )
    (net (code "43") (name "unconnected-(D1-C6-Pad6)") (class "Default")
      (node (ref "D1") (pin "6") (pinfunction "C6_6") (pintype "passive+no_connect"))
    )
    (net (code "44") (name "unconnected-(D2-C3-Pad3)") (class "Default")
      (node (ref "D2") (pin "3") (pinfunction "C3_3") (pintype "passive+no_connect"))
    )
    (net (code "45") (name "unconnected-(D2-C6-Pad6)") (class "Default")
      (node (ref "D2") (pin "6") (pinfunction "C6_6") (pintype "passive+no_connect"))
    )
    (net (code "46") (name "unconnected-(OP1-NC-Pad1)") (class "Default")
      (node (ref "OP1") (pin "1") (pinfunction "NC_1") (pintype "passive+no_connect"))
    )
    (net (code "47") (name "unconnected-(OP1-~{PD}-Pad12)") (class "Default")
      (node (ref "OP1") (pin "12") (pinfunction "~{PD}_12") (pintype "input+no_connect"))
    )
    (net (code "48") (name "unconnected-(OP2-NC-Pad1)") (class "Default")
      (node (ref "OP2") (pin "1") (pinfunction "NC_1") (pintype "passive+no_connect"))
    )
    (net (code "49") (name "unconnected-(OP2-~{PD}-Pad12)") (class "Default")
      (node (ref "OP2") (pin "12") (pinfunction "~{PD}_12") (pintype "input+no_connect"))
    )
  )
)
